# Microcontroller.net
KiCad netlist of a schematic drawn in Altium Designer
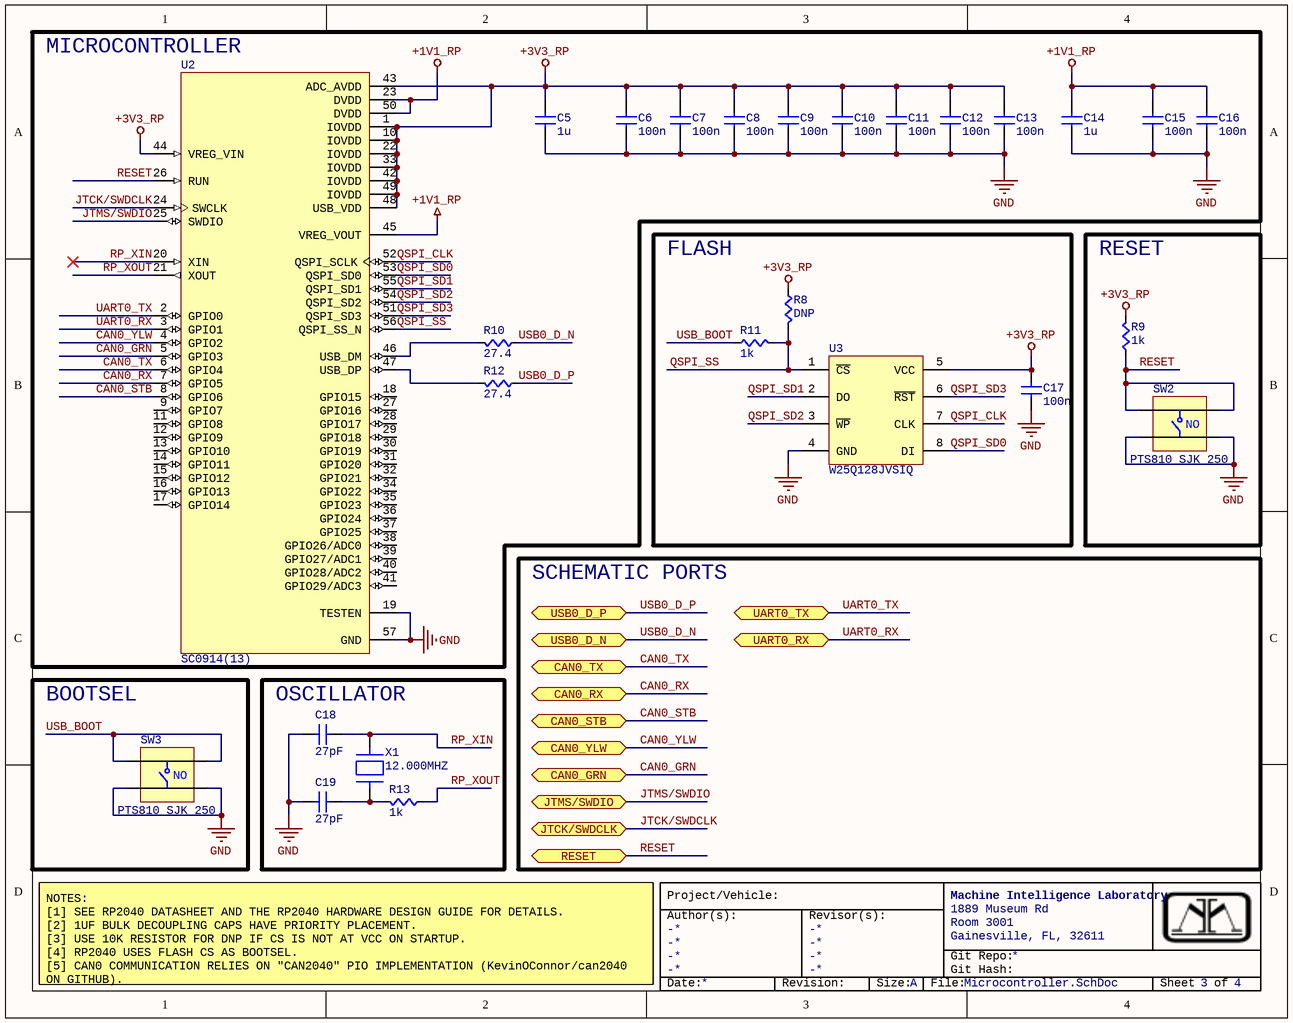
[diagram p0: Microcontroller.SchDoc]

(export (version "E")
  (design (tool "Eeschema 10.0.6"))
  (components
    (comp (ref "C5")
      (value "1u")
      (footprint "CAPC0805")
      (fields (field (name "Comment") "Cap"))
      (libsource (lib "Passives") (part "Cap"))
    )
    (comp (ref "C6")
      (value "100n")
      (footprint "CAPC0805")
      (fields (field (name "Comment") "Cap"))
      (libsource (lib "Passives") (part "Cap"))
    )
    (comp (ref "C7")
      (value "100n")
      (footprint "CAPC0805")
      (fields (field (name "Comment") "Cap"))
      (libsource (lib "Passives") (part "Cap"))
    )
    (comp (ref "C8")
      (value "100n")
      (footprint "CAPC0805")
      (fields (field (name "Comment") "Cap"))
      (libsource (lib "Passives") (part "Cap"))
    )
    (comp (ref "C9")
      (value "100n")
      (footprint "CAPC0805")
      (fields (field (name "Comment") "Cap"))
      (libsource (lib "Passives") (part "Cap"))
    )
    (comp (ref "C10")
      (value "100n")
      (footprint "CAPC0805")
      (fields (field (name "Comment") "Cap"))
      (libsource (lib "Passives") (part "Cap"))
    )
    (comp (ref "C11")
      (value "100n")
      (footprint "CAPC0805")
      (fields (field (name "Comment") "Cap"))
      (libsource (lib "Passives") (part "Cap"))
    )
    (comp (ref "C12")
      (value "100n")
      (footprint "CAPC0805")
      (fields (field (name "Comment") "Cap"))
      (libsource (lib "Passives") (part "Cap"))
    )
    (comp (ref "C13")
      (value "100n")
      (footprint "CAPC0805")
      (fields (field (name "Comment") "Cap"))
      (libsource (lib "Passives") (part "Cap"))
    )
    (comp (ref "C14")
      (value "1u")
      (footprint "CAPC0805")
      (fields (field (name "Comment") "Cap"))
      (libsource (lib "Passives") (part "Cap"))
    )
    (comp (ref "C15")
      (value "100n")
      (footprint "CAPC0805")
      (fields (field (name "Comment") "Cap"))
      (libsource (lib "Passives") (part "Cap"))
    )
    (comp (ref "C16")
      (value "100n")
      (footprint "CAPC0805")
      (fields (field (name "Comment") "Cap"))
      (libsource (lib "Passives") (part "Cap"))
    )
    (comp (ref "C17")
      (value "100n")
      (footprint "CAPC0805")
      (fields (field (name "Comment") "Cap"))
      (libsource (lib "Passives") (part "Cap"))
    )
    (comp (ref "C18")
      (value "27pF")
      (footprint "CAPC0805")
      (fields (field (name "Comment") "Cap"))
      (libsource (lib "Passives") (part "Cap"))
    )
    (comp (ref "C19")
      (value "27pF")
      (footprint "CAPC0805")
      (fields (field (name "Comment") "Cap"))
      (libsource (lib "Passives") (part "Cap"))
    )
    (comp (ref "R8")
      (value "DNP")
      (footprint "RES0805")
      (fields (field (name "Comment") "Res"))
      (libsource (lib "Passives") (part "Res"))
    )
    (comp (ref "R9")
      (value "1k")
      (footprint "RES0805")
      (fields (field (name "Comment") "Res"))
      (libsource (lib "Passives") (part "Res"))
    )
    (comp (ref "R10")
      (value "27.4")
      (footprint "RES0805")
      (fields (field (name "Comment") "Res"))
      (libsource (lib "Passives") (part "Res"))
    )
    (comp (ref "R11")
      (value "1k")
      (footprint "RES0805")
      (fields (field (name "Comment") "Res"))
      (libsource (lib "Passives") (part "Res"))
    )
    (comp (ref "R12")
      (value "27.4")
      (footprint "RES0805")
      (fields (field (name "Comment") "Res"))
      (libsource (lib "Passives") (part "Res"))
    )
    (comp (ref "R13")
      (value "1k")
      (footprint "RES0805")
      (fields (field (name "Comment") "Res"))
      (libsource (lib "Passives") (part "Res"))
    )
    (comp (ref "SW2")
      (value "PTS810 SJK 250")
      (footprint "SW_PTS810_SJM_250_SMTR_LFS")
      (description "Tactile Switch SPST-NO Top Actuated Surface Mount")
      (libsource (lib "TGIS_Microcontrollers") (part "PTS810 SJK 250 SMTR LFS"))
    )
    (comp (ref "SW3")
      (value "PTS810 SJK 250")
      (footprint "SW_PTS810_SJM_250_SMTR_LFS")
      (description "Tactile Switch SPST-NO Top Actuated Surface Mount")
      (libsource (lib "TGIS_Microcontrollers") (part "PTS810 SJK 250 SMTR LFS"))
    )
    (comp (ref "U2")
      (value "SC0914(13)")
      (footprint "QFN40P700X700X90-57N")
      (description "ARM® Cortex®-M0+ - Microcontroller IC 32-Bit Dual-Core 133MHz External Program Memory 56-QFN (7x7)")
      (fields (field (name "MF") "Raspberry Pi"))
      (libsource (lib "TGIS_Microcontrollers") (part "SC0914(13)"))
    )
    (comp (ref "U3")
      (value "W25Q128JVSIQ")
      (footprint "SOIC127P790X216-8N")
      (description "FLASH - NOR Memory IC 128Mbit SPI - Quad I/O, QPI, DTR 133 MHz 8-SOIC")
      (libsource (lib "TGIS_Microcontrollers") (part "W25Q128JVSIQ"))
    )
    (comp (ref "X1")
      (value "12.000MHZ")
      (footprint "ABLS-12.000MHZ")
      (description "12 MHz ±20ppm Crystal 18pF 50 Ohms HC-49/US")
      (libsource (lib "TGIS_Microcontrollers") (part "ABLS-12.000MHZ"))
    )
  )
  (nets
    (net (code "1") (name "+1V1_RP") (class "Default")
      (node (ref "C14") (pin "1") (pinfunction "A_1") (pintype "passive"))
      (node (ref "C15") (pin "1") (pinfunction "A_1") (pintype "passive"))
      (node (ref "C16") (pin "1") (pinfunction "A_1") (pintype "passive"))
      (node (ref "U2") (pin "23") (pinfunction "DVDD_23") (pintype "power_in"))
      (node (ref "U2") (pin "45") (pinfunction "VREG_VOUT_45") (pintype "power_in"))
      (node (ref "U2") (pin "50") (pinfunction "DVDD_50") (pintype "power_in"))
    )
    (net (code "2") (name "+3V3_RP") (class "Default")
      (node (ref "C10") (pin "1") (pinfunction "A_1") (pintype "passive"))
      (node (ref "C11") (pin "1") (pinfunction "A_1") (pintype "passive"))
      (node (ref "C12") (pin "1") (pinfunction "A_1") (pintype "passive"))
      (node (ref "C13") (pin "1") (pinfunction "A_1") (pintype "passive"))
      (node (ref "C17") (pin "1") (pinfunction "A_1") (pintype "passive"))
      (node (ref "C5") (pin "1") (pinfunction "A_1") (pintype "passive"))
      (node (ref "C6") (pin "1") (pinfunction "A_1") (pintype "passive"))
      (node (ref "C7") (pin "1") (pinfunction "A_1") (pintype "passive"))
      (node (ref "C8") (pin "1") (pinfunction "A_1") (pintype "passive"))
      (node (ref "C9") (pin "1") (pinfunction "A_1") (pintype "passive"))
      (node (ref "R8") (pin "2") (pinfunction "B_2") (pintype "passive"))
      (node (ref "R9") (pin "1") (pinfunction "A_1") (pintype "passive"))
      (node (ref "U2") (pin "1") (pinfunction "IOVDD_1") (pintype "power_in"))
      (node (ref "U2") (pin "10") (pinfunction "IOVDD_10") (pintype "power_in"))
      (node (ref "U2") (pin "22") (pinfunction "IOVDD_22") (pintype "power_in"))
      (node (ref "U2") (pin "33") (pinfunction "IOVDD_33") (pintype "power_in"))
      (node (ref "U2") (pin "42") (pinfunction "IOVDD_42") (pintype "power_in"))
      (node (ref "U2") (pin "43") (pinfunction "ADC_AVDD_43") (pintype "power_in"))
      (node (ref "U2") (pin "44") (pinfunction "VREG_VIN_44") (pintype "input"))
      (node (ref "U2") (pin "48") (pinfunction "USB_VDD_48") (pintype "power_in"))
      (node (ref "U2") (pin "49") (pinfunction "IOVDD_49") (pintype "power_in"))
      (node (ref "U3") (pin "5") (pinfunction "VCC_5") (pintype "passive"))
    )
    (net (code "3") (name "/CAN0_GRN") (class "Default")
      (node (ref "U2") (pin "5") (pinfunction "GPIO3_5") (pintype "bidirectional"))
    )
    (net (code "4") (name "/CAN0_RX") (class "Default")
      (node (ref "U2") (pin "7") (pinfunction "GPIO5_7") (pintype "bidirectional"))
    )
    (net (code "5") (name "/CAN0_STB") (class "Default")
      (node (ref "U2") (pin "8") (pinfunction "GPIO6_8") (pintype "bidirectional"))
    )
    (net (code "6") (name "/CAN0_TX") (class "Default")
      (node (ref "U2") (pin "6") (pinfunction "GPIO4_6") (pintype "bidirectional"))
    )
    (net (code "7") (name "/CAN0_YLW") (class "Default")
      (node (ref "U2") (pin "4") (pinfunction "GPIO2_4") (pintype "bidirectional"))
    )
    (net (code "8") (name "/JTCK{slash}SWDCLK") (class "Default")
      (node (ref "U2") (pin "24") (pinfunction "SWCLK_24") (pintype "input"))
    )
    (net (code "9") (name "/JTMS{slash}SWDIO") (class "Default")
      (node (ref "U2") (pin "25") (pinfunction "SWDIO_25") (pintype "bidirectional"))
    )
    (net (code "10") (name "/QSPI_CLK") (class "Default")
      (node (ref "U2") (pin "52") (pinfunction "QSPI_SCLK_52") (pintype "bidirectional"))
      (node (ref "U3") (pin "7") (pinfunction "CLK_7") (pintype "passive"))
    )
    (net (code "11") (name "/QSPI_SD0") (class "Default")
      (node (ref "U2") (pin "53") (pinfunction "QSPI_SD0_53") (pintype "bidirectional"))
      (node (ref "U3") (pin "8") (pinfunction "DI_8") (pintype "passive"))
    )
    (net (code "12") (name "/QSPI_SD1") (class "Default")
      (node (ref "U2") (pin "55") (pinfunction "QSPI_SD1_55") (pintype "bidirectional"))
      (node (ref "U3") (pin "2") (pinfunction "DO_2") (pintype "passive"))
    )
    (net (code "13") (name "/QSPI_SD2") (class "Default")
      (node (ref "U2") (pin "54") (pinfunction "QSPI_SD2_54") (pintype "bidirectional"))
      (node (ref "U3") (pin "3") (pinfunction "WP_3") (pintype "passive"))
    )
    (net (code "14") (name "/QSPI_SD3") (class "Default")
      (node (ref "U2") (pin "51") (pinfunction "QSPI_SD3_51") (pintype "bidirectional"))
      (node (ref "U3") (pin "6") (pinfunction "RST_6") (pintype "passive"))
    )
    (net (code "15") (name "/QSPI_SS") (class "Default")
      (node (ref "R11") (pin "1") (pinfunction "A_1") (pintype "passive"))
      (node (ref "R8") (pin "1") (pinfunction "A_1") (pintype "passive"))
      (node (ref "U2") (pin "56") (pinfunction "QSPI_SS_N_56") (pintype "bidirectional"))
      (node (ref "U3") (pin "1") (pinfunction "CS_1") (pintype "passive"))
    )
    (net (code "16") (name "/RESET") (class "Default")
      (node (ref "R9") (pin "2") (pinfunction "B_2") (pintype "passive"))
      (node (ref "SW2") (pin "1") (pinfunction "1_1") (pintype "passive"))
      (node (ref "SW2") (pin "2") (pinfunction "2_2") (pintype "passive"))
      (node (ref "U2") (pin "26") (pinfunction "RUN_26") (pintype "input"))
    )
    (net (code "17") (name "/RP_XIN") (class "Default")
      (node (ref "C18") (pin "2") (pinfunction "B_2") (pintype "passive"))
      (node (ref "U2") (pin "20") (pinfunction "XIN_20") (pintype "input"))
      (node (ref "X1") (pin "1") (pinfunction "1_1") (pintype "passive"))
    )
    (net (code "18") (name "/RP_XOUT") (class "Default")
      (node (ref "R13") (pin "2") (pinfunction "B_2") (pintype "passive"))
      (node (ref "U2") (pin "21") (pinfunction "XOUT_21") (pintype "output"))
    )
    (net (code "19") (name "/UART0_RX") (class "Default")
      (node (ref "U2") (pin "3") (pinfunction "GPIO1_3") (pintype "bidirectional"))
    )
    (net (code "20") (name "/UART0_TX") (class "Default")
      (node (ref "U2") (pin "2") (pinfunction "GPIO0_2") (pintype "bidirectional"))
    )
    (net (code "21") (name "/USB0_D_N") (class "Default")
      (node (ref "R10") (pin "2") (pinfunction "B_2") (pintype "passive"))
    )
    (net (code "22") (name "/USB0_D_P") (class "Default")
      (node (ref "R12") (pin "2") (pinfunction "B_2") (pintype "passive"))
    )
    (net (code "23") (name "/USB_BOOT") (class "Default")
      (node (ref "R11") (pin "2") (pinfunction "B_2") (pintype "passive"))
      (node (ref "SW3") (pin "1") (pinfunction "1_1") (pintype "passive"))
      (node (ref "SW3") (pin "2") (pinfunction "2_2") (pintype "passive"))
    )
    (net (code "24") (name "GND") (class "Default")
      (node (ref "C10") (pin "2") (pinfunction "B_2") (pintype "passive"))
      (node (ref "C11") (pin "2") (pinfunction "B_2") (pintype "passive"))
      (node (ref "C12") (pin "2") (pinfunction "B_2") (pintype "passive"))
      (node (ref "C13") (pin "2") (pinfunction "B_2") (pintype "passive"))
      (node (ref "C14") (pin "2") (pinfunction "B_2") (pintype "passive"))
      (node (ref "C15") (pin "2") (pinfunction "B_2") (pintype "passive"))
      (node (ref "C16") (pin "2") (pinfunction "B_2") (pintype "passive"))
      (node (ref "C17") (pin "2") (pinfunction "B_2") (pintype "passive"))
      (node (ref "C18") (pin "1") (pinfunction "A_1") (pintype "passive"))
      (node (ref "C19") (pin "1") (pinfunction "A_1") (pintype "passive"))
      (node (ref "C5") (pin "2") (pinfunction "B_2") (pintype "passive"))
      (node (ref "C6") (pin "2") (pinfunction "B_2") (pintype "passive"))
      (node (ref "C7") (pin "2") (pinfunction "B_2") (pintype "passive"))
      (node (ref "C8") (pin "2") (pinfunction "B_2") (pintype "passive"))
      (node (ref "C9") (pin "2") (pinfunction "B_2") (pintype "passive"))
      (node (ref "SW2") (pin "3") (pinfunction "3_3") (pintype "passive"))
      (node (ref "SW2") (pin "4") (pinfunction "4_4") (pintype "passive"))
      (node (ref "SW3") (pin "3") (pinfunction "3_3") (pintype "passive"))
      (node (ref "SW3") (pin "4") (pinfunction "4_4") (pintype "passive"))
      (node (ref "U2") (pin "19") (pinfunction "TESTEN_19") (pintype "passive"))
      (node (ref "U2") (pin "57") (pinfunction "GND_57") (pintype "power_in"))
      (node (ref "U3") (pin "4") (pinfunction "GND_4") (pintype "passive"))
    )
    (net (code "25") (name "Net-(C19-B)") (class "Default")
      (node (ref "C19") (pin "2") (pinfunction "B_2") (pintype "passive"))
      (node (ref "R13") (pin "1") (pinfunction "A_1") (pintype "passive"))
      (node (ref "X1") (pin "2") (pinfunction "2_2") (pintype "passive"))
    )
    (net (code "26") (name "Net-(R10-A)") (class "Default")
      (node (ref "R10") (pin "1") (pinfunction "A_1") (pintype "passive"))
      (node (ref "U2") (pin "46") (pinfunction "USB_DM_46") (pintype "bidirectional"))
    )
    (net (code "27") (name "Net-(R12-A)") (class "Default")
      (node (ref "R12") (pin "1") (pinfunction "A_1") (pintype "passive"))
      (node (ref "U2") (pin "47") (pinfunction "USB_DP_47") (pintype "bidirectional"))
    )
    (net (code "28") (name "unconnected-(U2-GPIO7-Pad9)") (class "Default")
      (node (ref "U2") (pin "9") (pinfunction "GPIO7_9") (pintype "bidirectional"))
    )
    (net (code "29") (name "unconnected-(U2-GPIO8-Pad11)") (class "Default")
      (node (ref "U2") (pin "11") (pinfunction "GPIO8_11") (pintype "bidirectional"))
    )
    (net (code "30") (name "unconnected-(U2-GPIO9-Pad12)") (class "Default")
      (node (ref "U2") (pin "12") (pinfunction "GPIO9_12") (pintype "bidirectional"))
    )
    (net (code "31") (name "unconnected-(U2-GPIO10-Pad13)") (class "Default")
      (node (ref "U2") (pin "13") (pinfunction "GPIO10_13") (pintype "bidirectional"))
    )
    (net (code "32") (name "unconnected-(U2-GPIO11-Pad14)") (class "Default")
      (node (ref "U2") (pin "14") (pinfunction "GPIO11_14") (pintype "bidirectional"))
    )
    (net (code "33") (name "unconnected-(U2-GPIO12-Pad15)") (class "Default")
      (node (ref "U2") (pin "15") (pinfunction "GPIO12_15") (pintype "bidirectional"))
    )
    (net (code "34") (name "unconnected-(U2-GPIO13-Pad16)") (class "Default")
      (node (ref "U2") (pin "16") (pinfunction "GPIO13_16") (pintype "bidirectional"))
    )
    (net (code "35") (name "unconnected-(U2-GPIO14-Pad17)") (class "Default")
      (node (ref "U2") (pin "17") (pinfunction "GPIO14_17") (pintype "bidirectional"))
    )
    (net (code "36") (name "unconnected-(U2-GPIO15-Pad18)") (class "Default")
      (node (ref "U2") (pin "18") (pinfunction "GPIO15_18") (pintype "bidirectional"))
    )
    (net (code "37") (name "unconnected-(U2-GPIO16-Pad27)") (class "Default")
      (node (ref "U2") (pin "27") (pinfunction "GPIO16_27") (pintype "bidirectional"))
    )
    (net (code "38") (name "unconnected-(U2-GPIO17-Pad28)") (class "Default")
      (node (ref "U2") (pin "28") (pinfunction "GPIO17_28") (pintype "bidirectional"))
    )
    (net (code "39") (name "unconnected-(U2-GPIO18-Pad29)") (class "Default")
      (node (ref "U2") (pin "29") (pinfunction "GPIO18_29") (pintype "bidirectional"))
    )
    (net (code "40") (name "unconnected-(U2-GPIO19-Pad30)") (class "Default")
      (node (ref "U2") (pin "30") (pinfunction "GPIO19_30") (pintype "bidirectional"))
    )
    (net (code "41") (name "unconnected-(U2-GPIO20-Pad31)") (class "Default")
      (node (ref "U2") (pin "31") (pinfunction "GPIO20_31") (pintype "bidirectional"))
    )
    (net (code "42") (name "unconnected-(U2-GPIO21-Pad32)") (class "Default")
      (node (ref "U2") (pin "32") (pinfunction "GPIO21_32") (pintype "bidirectional"))
    )
    (net (code "43") (name "unconnected-(U2-GPIO22-Pad34)") (class "Default")
      (node (ref "U2") (pin "34") (pinfunction "GPIO22_34") (pintype "bidirectional"))
    )
    (net (code "44") (name "unconnected-(U2-GPIO23-Pad35)") (class "Default")
      (node (ref "U2") (pin "35") (pinfunction "GPIO23_35") (pintype "bidirectional"))
    )
    (net (code "45") (name "unconnected-(U2-GPIO24-Pad36)") (class "Default")
      (node (ref "U2") (pin "36") (pinfunction "GPIO24_36") (pintype "bidirectional"))
    )
    (net (code "46") (name "unconnected-(U2-GPIO25-Pad37)") (class "Default")
      (node (ref "U2") (pin "37") (pinfunction "GPIO25_37") (pintype "bidirectional"))
    )
    (net (code "47") (name "unconnected-(U2-GPIO26{slash}ADC0-Pad38)") (class "Default")
      (node (ref "U2") (pin "38") (pinfunction "GPIO26/ADC0_38") (pintype "bidirectional"))
    )
    (net (code "48") (name "unconnected-(U2-GPIO27{slash}ADC1-Pad39)") (class "Default")
      (node (ref "U2") (pin "39") (pinfunction "GPIO27/ADC1_39") (pintype "bidirectional"))
    )
    (net (code "49") (name "unconnected-(U2-GPIO28{slash}ADC2-Pad40)") (class "Default")
      (node (ref "U2") (pin "40") (pinfunction "GPIO28/ADC2_40") (pintype "bidirectional"))
    )
    (net (code "50") (name "unconnected-(U2-GPIO29{slash}ADC3-Pad41)") (class "Default")
      (node (ref "U2") (pin "41") (pinfunction "GPIO29/ADC3_41") (pintype "bidirectional"))
    )
  )
)
